# Stepper_Motor_Driver_TIP_Version_v1_0.net
KiCad netlist of a schematic drawn in EAGLE
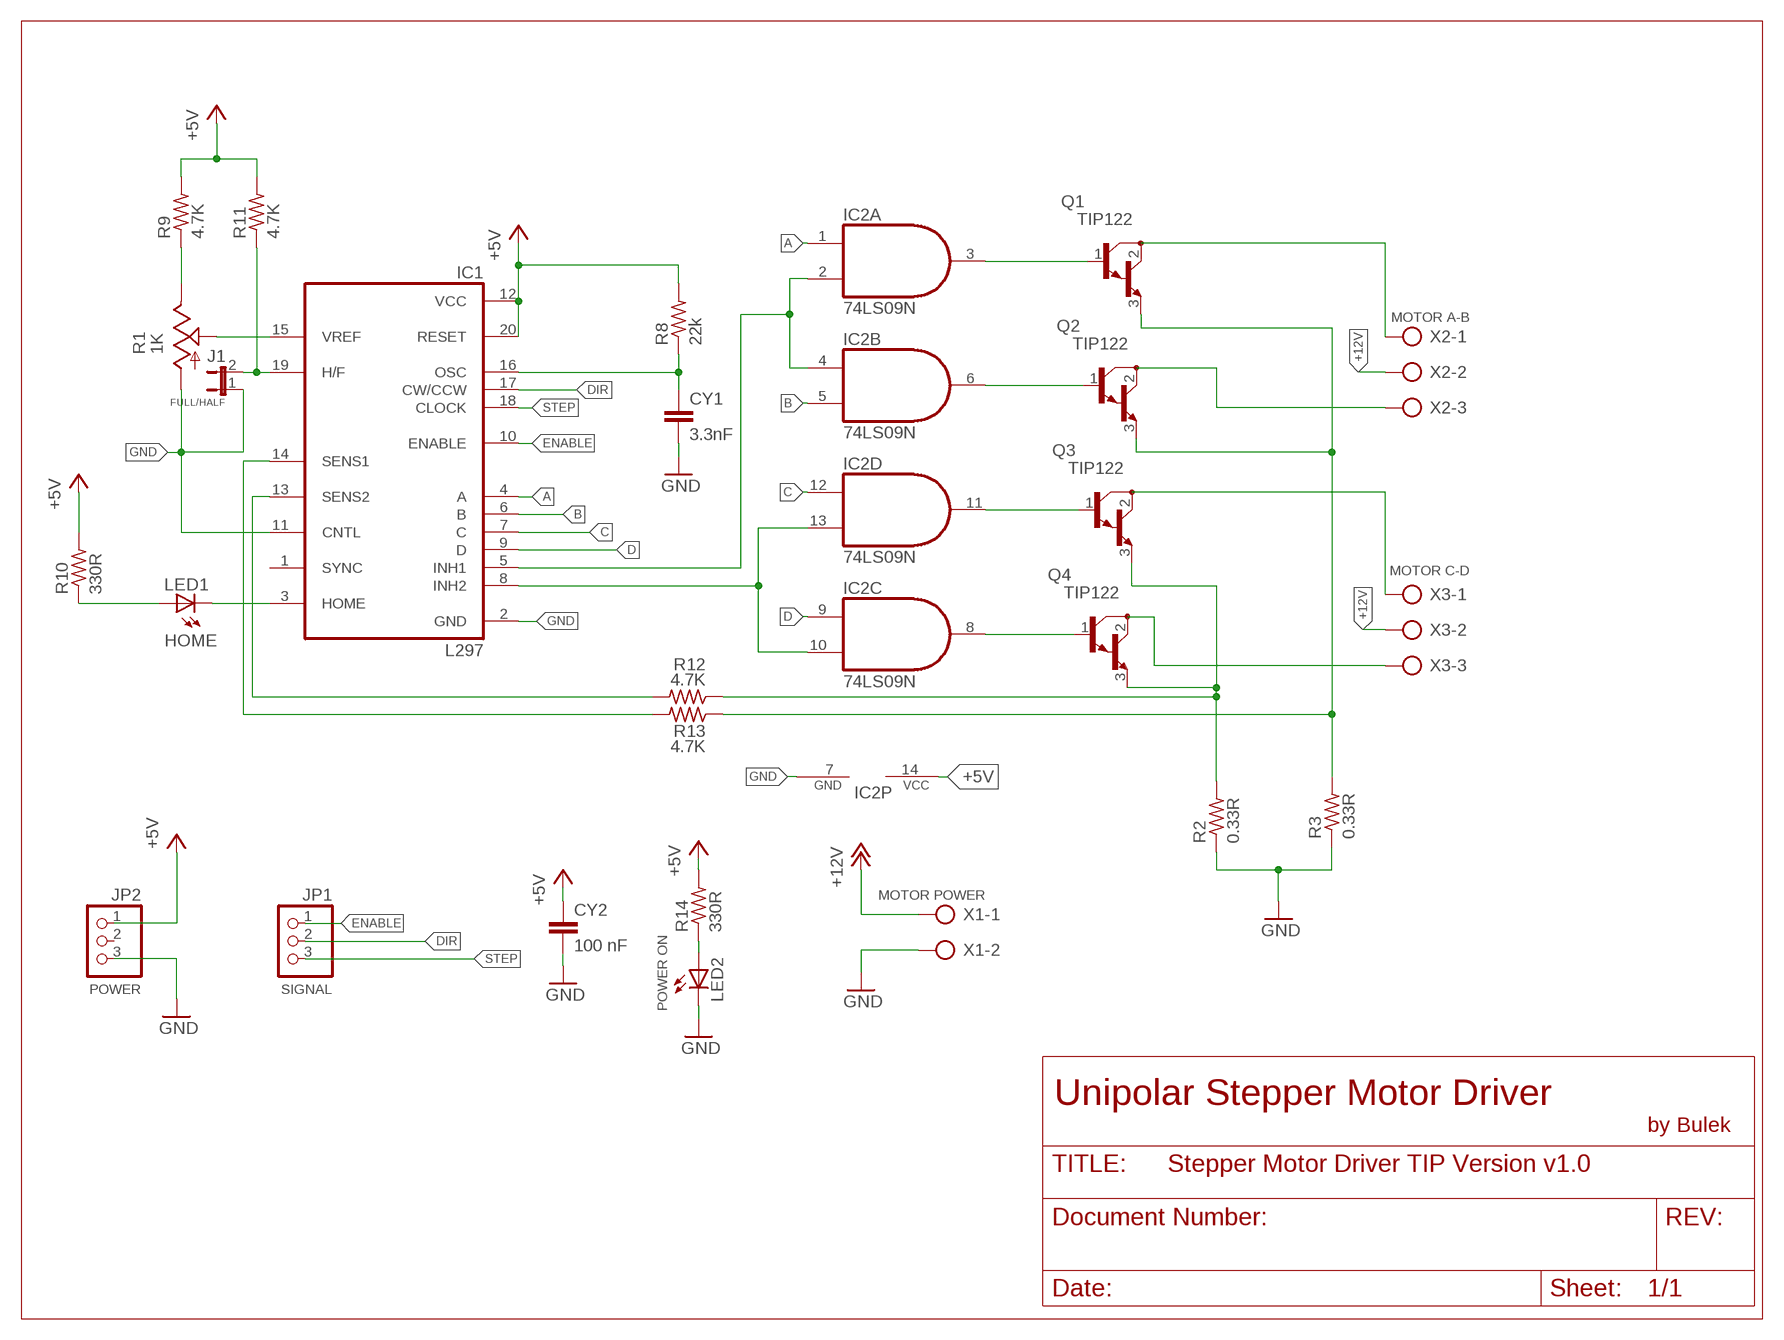
[diagram p0: schematic, sheet 1]

(export (version "E")
  (design (tool "Eeschema 10.0.6"))
  (components
    (comp (ref "CY1")
      (value "3.3nF")
      (footprint "eagle-import:YC7B5")
      (libsource (lib "eagle-import") (part "CYYC7B5"))
    )
    (comp (ref "CY2")
      (value "100 nF")
      (footprint "eagle-import:YC7B5")
      (libsource (lib "eagle-import") (part "CYYC7B5"))
    )
    (comp (ref "FULL/HALF")
      (value "J1")
      (footprint "eagle-import:JP1")
      (libsource (lib "eagle-import") (part "JP1E"))
    )
    (comp (ref "IC1")
      (value "L297")
      (footprint "eagle-import:DIL20")
      (fields (field (name "MPN") "L297/1"))
      (libsource (lib "eagle-import") (part "L297"))
    )
    (comp (ref "IC2")
      (value "74LS09N")
      (footprint "eagle-import:DIL14")
      (libsource (lib "eagle-import") (part "7409NLS"))
    )
    (comp (ref "JP1")
      (value "SIGNAL")
      (footprint "eagle-import:1X03_90")
      (libsource (lib "eagle-import") (part "PINHD-1X3/90"))
    )
    (comp (ref "JP2")
      (value "POWER")
      (footprint "eagle-import:1X03_90")
      (libsource (lib "eagle-import") (part "PINHD-1X3/90"))
    )
    (comp (ref "LED1")
      (value "HOME")
      (footprint "eagle-import:LED5MM")
      (libsource (lib "eagle-import") (part "LED5MM"))
    )
    (comp (ref "LED2")
      (value "POWER ON")
      (footprint "eagle-import:LED5MM")
      (libsource (lib "eagle-import") (part "LED5MM"))
    )
    (comp (ref "Q1")
      (value "TIP122")
      (footprint "eagle-import:TO220V")
      (libsource (lib "eagle-import") (part "TIP122"))
    )
    (comp (ref "Q2")
      (value "TIP122")
      (footprint "eagle-import:TO220V")
      (libsource (lib "eagle-import") (part "TIP122"))
    )
    (comp (ref "Q3")
      (value "TIP122")
      (footprint "eagle-import:TO220V")
      (libsource (lib "eagle-import") (part "TIP122"))
    )
    (comp (ref "Q4")
      (value "TIP122")
      (footprint "eagle-import:TO220V")
      (libsource (lib "eagle-import") (part "TIP122"))
    )
    (comp (ref "R1")
      (value "1K")
      (footprint "eagle-import:S63X")
      (libsource (lib "eagle-import") (part "TRIM_US-S63X"))
    )
    (comp (ref "R2")
      (value "0.33R")
      (footprint "eagle-import:0617_22")
      (libsource (lib "eagle-import") (part "R-US_0617/22"))
    )
    (comp (ref "R3")
      (value "0.33R")
      (footprint "eagle-import:0617_22")
      (libsource (lib "eagle-import") (part "R-US_0617/22"))
    )
    (comp (ref "R8")
      (value "22k")
      (footprint "eagle-import:0207_10")
      (libsource (lib "eagle-import") (part "R-US_0207/10"))
    )
    (comp (ref "R9")
      (value "4.7K")
      (footprint "eagle-import:0207_10")
      (libsource (lib "eagle-import") (part "R-US_0207/10"))
    )
    (comp (ref "R10")
      (value "330R")
      (footprint "eagle-import:0207_10")
      (libsource (lib "eagle-import") (part "R-US_0207/10"))
    )
    (comp (ref "R11")
      (value "4.7K")
      (footprint "eagle-import:0207_10")
      (libsource (lib "eagle-import") (part "R-US_0207/10"))
    )
    (comp (ref "R12")
      (value "4.7K")
      (footprint "eagle-import:0207_10")
      (libsource (lib "eagle-import") (part "R-US_0207/10"))
    )
    (comp (ref "R13")
      (value "4.7K")
      (footprint "eagle-import:0207_10")
      (libsource (lib "eagle-import") (part "R-US_0207/10"))
    )
    (comp (ref "R14")
      (value "330R")
      (footprint "eagle-import:0207_10")
      (libsource (lib "eagle-import") (part "R-US_0207/10"))
    )
    (comp (ref "X1")
      (value "MOTOR POWER")
      (footprint "eagle-import:AK300_2")
      (libsource (lib "eagle-import") (part "AK300/2"))
    )
    (comp (ref "X2")
      (value "MOTOR A-B")
      (footprint "eagle-import:AK300_3")
      (libsource (lib "eagle-import") (part "AK300/3"))
    )
    (comp (ref "X3")
      (value "MOTOR C-D")
      (footprint "eagle-import:AK300_3")
      (libsource (lib "eagle-import") (part "AK300/3"))
    )
  )
  (nets
    (net (code "1") (name "+5V") (class "Default")
      (node (ref "CY2") (pin "1") (pinfunction "1_1") (pintype "passive"))
      (node (ref "IC1") (pin "12") (pinfunction "VCC_12") (pintype "power_in"))
      (node (ref "IC1") (pin "20") (pinfunction "RESET_20") (pintype "input"))
      (node (ref "IC2") (pin "14") (pinfunction "VCC_14") (pintype "power_in"))
      (node (ref "JP2") (pin "1") (pinfunction "1_1") (pintype "passive"))
      (node (ref "R10") (pin "2") (pinfunction "2_2") (pintype "passive"))
      (node (ref "R11") (pin "2") (pinfunction "2_2") (pintype "passive"))
      (node (ref "R14") (pin "2") (pinfunction "2_2") (pintype "passive"))
      (node (ref "R8") (pin "2") (pinfunction "2_2") (pintype "passive"))
      (node (ref "R9") (pin "2") (pinfunction "2_2") (pintype "passive"))
    )
    (net (code "2") (name "+12V") (class "Default")
      (node (ref "X1") (pin "1") (pinfunction "KL_1") (pintype "passive"))
      (node (ref "X2") (pin "2") (pinfunction "KL_2") (pintype "passive"))
      (node (ref "X3") (pin "2") (pinfunction "KL_2") (pintype "passive"))
    )
    (net (code "3") (name "A") (class "Default")
      (node (ref "IC1") (pin "4") (pinfunction "A_4") (pintype "output"))
      (node (ref "IC2") (pin "1") (pinfunction "I0_1") (pintype "input"))
    )
    (net (code "4") (name "B") (class "Default")
      (node (ref "IC1") (pin "6") (pinfunction "B_6") (pintype "output"))
      (node (ref "IC2") (pin "5") (pinfunction "I1_5") (pintype "input"))
    )
    (net (code "5") (name "C") (class "Default")
      (node (ref "IC1") (pin "7") (pinfunction "C_7") (pintype "output"))
      (node (ref "IC2") (pin "12") (pinfunction "I0_12") (pintype "input"))
    )
    (net (code "6") (name "D") (class "Default")
      (node (ref "IC1") (pin "9") (pinfunction "D_9") (pintype "output"))
      (node (ref "IC2") (pin "9") (pinfunction "I0_9") (pintype "input"))
    )
    (net (code "7") (name "DIR") (class "Default")
      (node (ref "IC1") (pin "17") (pinfunction "CW/CCW_17") (pintype "input"))
      (node (ref "JP1") (pin "2") (pinfunction "2_2") (pintype "passive"))
    )
    (net (code "8") (name "ENABLE") (class "Default")
      (node (ref "IC1") (pin "10") (pinfunction "ENABLE_10") (pintype "input"))
      (node (ref "JP1") (pin "1") (pinfunction "1_1") (pintype "passive"))
    )
    (net (code "9") (name "GND") (class "Default")
      (node (ref "CY1") (pin "2") (pinfunction "2_2") (pintype "passive"))
      (node (ref "CY2") (pin "2") (pinfunction "2_2") (pintype "passive"))
      (node (ref "FULL/HALF") (pin "1") (pinfunction "1_1") (pintype "passive"))
      (node (ref "IC1") (pin "11") (pinfunction "CNTL_11") (pintype "input"))
      (node (ref "IC1") (pin "2") (pinfunction "GND_2") (pintype "power_in"))
      (node (ref "IC2") (pin "7") (pinfunction "GND_7") (pintype "power_in"))
      (node (ref "JP2") (pin "3") (pinfunction "3_3") (pintype "passive"))
      (node (ref "LED2") (pin "K") (pinfunction "C_K") (pintype "passive"))
      (node (ref "R1") (pin "A") (pinfunction "A_A") (pintype "passive"))
      (node (ref "R2") (pin "1") (pinfunction "1_1") (pintype "passive"))
      (node (ref "R3") (pin "1") (pinfunction "1_1") (pintype "passive"))
      (node (ref "X1") (pin "2") (pinfunction "KL_2") (pintype "passive"))
    )
    (net (code "10") (name "Net-(IC1-HOME)") (class "Default")
      (node (ref "IC1") (pin "3") (pinfunction "HOME_3") (pintype "output"))
      (node (ref "LED1") (pin "K") (pinfunction "C_K") (pintype "passive"))
    )
    (net (code "11") (name "Net-(IC1-H{slash}F)") (class "Default")
      (node (ref "FULL/HALF") (pin "2") (pinfunction "2_2") (pintype "passive"))
      (node (ref "IC1") (pin "19") (pinfunction "H/F_19") (pintype "input"))
      (node (ref "R11") (pin "1") (pinfunction "1_1") (pintype "passive"))
    )
    (net (code "12") (name "Net-(IC1-INH1)") (class "Default")
      (node (ref "IC1") (pin "5") (pinfunction "INH1_5") (pintype "output"))
      (node (ref "IC2") (pin "2") (pinfunction "I1_2") (pintype "input"))
      (node (ref "IC2") (pin "4") (pinfunction "I0_4") (pintype "input"))
    )
    (net (code "13") (name "Net-(IC1-INH2)") (class "Default")
      (node (ref "IC1") (pin "8") (pinfunction "INH2_8") (pintype "output"))
      (node (ref "IC2") (pin "10") (pinfunction "I1_10") (pintype "input"))
      (node (ref "IC2") (pin "13") (pinfunction "I1_13") (pintype "input"))
    )
    (net (code "14") (name "Net-(IC1-OSC)") (class "Default")
      (node (ref "CY1") (pin "1") (pinfunction "1_1") (pintype "passive"))
      (node (ref "IC1") (pin "16") (pinfunction "OSC_16") (pintype "bidirectional"))
      (node (ref "R8") (pin "1") (pinfunction "1_1") (pintype "passive"))
    )
    (net (code "15") (name "Net-(IC1-SENS1)") (class "Default")
      (node (ref "IC1") (pin "14") (pinfunction "SENS1_14") (pintype "output"))
      (node (ref "R13") (pin "2") (pinfunction "2_2") (pintype "passive"))
    )
    (net (code "16") (name "Net-(IC1-SENS2)") (class "Default")
      (node (ref "IC1") (pin "13") (pinfunction "SENS2_13") (pintype "output"))
      (node (ref "R12") (pin "2") (pinfunction "2_2") (pintype "passive"))
    )
    (net (code "17") (name "Net-(IC1-VREF)") (class "Default")
      (node (ref "IC1") (pin "15") (pinfunction "VREF_15") (pintype "input"))
      (node (ref "R1") (pin "S") (pinfunction "S_S") (pintype "passive"))
    )
    (net (code "18") (name "Net-(IC2A-O)") (class "Default")
      (node (ref "IC2") (pin "3") (pinfunction "O_3") (pintype "open_collector"))
      (node (ref "Q1") (pin "1") (pinfunction "B_1") (pintype "passive"))
    )
    (net (code "19") (name "Net-(IC2B-O)") (class "Default")
      (node (ref "IC2") (pin "6") (pinfunction "O_6") (pintype "open_collector"))
      (node (ref "Q2") (pin "1") (pinfunction "B_1") (pintype "passive"))
    )
    (net (code "20") (name "Net-(IC2C-O)") (class "Default")
      (node (ref "IC2") (pin "8") (pinfunction "O_8") (pintype "open_collector"))
      (node (ref "Q4") (pin "1") (pinfunction "B_1") (pintype "passive"))
    )
    (net (code "21") (name "Net-(IC2D-O)") (class "Default")
      (node (ref "IC2") (pin "11") (pinfunction "O_11") (pintype "open_collector"))
      (node (ref "Q3") (pin "1") (pinfunction "B_1") (pintype "passive"))
    )
    (net (code "22") (name "Net-(LED1-PadA)") (class "Default")
      (node (ref "LED1") (pin "A") (pinfunction "A_A") (pintype "passive"))
      (node (ref "R10") (pin "1") (pinfunction "1_1") (pintype "passive"))
    )
    (net (code "23") (name "Net-(LED2-PadA)") (class "Default")
      (node (ref "LED2") (pin "A") (pinfunction "A_A") (pintype "passive"))
      (node (ref "R14") (pin "1") (pinfunction "1_1") (pintype "passive"))
    )
    (net (code "24") (name "Net-(Q1-C)") (class "Default")
      (node (ref "Q1") (pin "2") (pinfunction "C_2") (pintype "passive"))
      (node (ref "X2") (pin "1") (pinfunction "KL_1") (pintype "passive"))
    )
    (net (code "25") (name "Net-(Q1-E)") (class "Default")
      (node (ref "Q1") (pin "3") (pinfunction "E_3") (pintype "passive"))
      (node (ref "Q2") (pin "3") (pinfunction "E_3") (pintype "passive"))
      (node (ref "R13") (pin "1") (pinfunction "1_1") (pintype "passive"))
      (node (ref "R3") (pin "2") (pinfunction "2_2") (pintype "passive"))
    )
    (net (code "26") (name "Net-(Q2-C)") (class "Default")
      (node (ref "Q2") (pin "2") (pinfunction "C_2") (pintype "passive"))
      (node (ref "X2") (pin "3") (pinfunction "KL_3") (pintype "passive"))
    )
    (net (code "27") (name "Net-(Q3-C)") (class "Default")
      (node (ref "Q3") (pin "2") (pinfunction "C_2") (pintype "passive"))
      (node (ref "X3") (pin "1") (pinfunction "KL_1") (pintype "passive"))
    )
    (net (code "28") (name "Net-(Q3-E)") (class "Default")
      (node (ref "Q3") (pin "3") (pinfunction "E_3") (pintype "passive"))
      (node (ref "Q4") (pin "3") (pinfunction "E_3") (pintype "passive"))
      (node (ref "R12") (pin "1") (pinfunction "1_1") (pintype "passive"))
      (node (ref "R2") (pin "2") (pinfunction "2_2") (pintype "passive"))
    )
    (net (code "29") (name "Net-(Q4-C)") (class "Default")
      (node (ref "Q4") (pin "2") (pinfunction "C_2") (pintype "passive"))
      (node (ref "X3") (pin "3") (pinfunction "KL_3") (pintype "passive"))
    )
    (net (code "30") (name "Net-(R1-PadE)") (class "Default")
      (node (ref "R1") (pin "E") (pinfunction "E_E") (pintype "passive"))
      (node (ref "R9") (pin "1") (pinfunction "1_1") (pintype "passive"))
    )
    (net (code "31") (name "STEP") (class "Default")
      (node (ref "IC1") (pin "18") (pinfunction "CLOCK_18") (pintype "input"))
      (node (ref "JP1") (pin "3") (pinfunction "3_3") (pintype "passive"))
    )
    (net (code "32") (name "unconnected-(IC1-SYNC-Pad1)") (class "Default")
      (node (ref "IC1") (pin "1") (pinfunction "SYNC_1") (pintype "output"))
    )
    (net (code "33") (name "unconnected-(JP2-Pad2)") (class "Default")
      (node (ref "JP2") (pin "2") (pinfunction "2_2") (pintype "passive"))
    )
  )
)
